# m1seminar.net
KiCad netlist of a schematic drawn in EAGLE
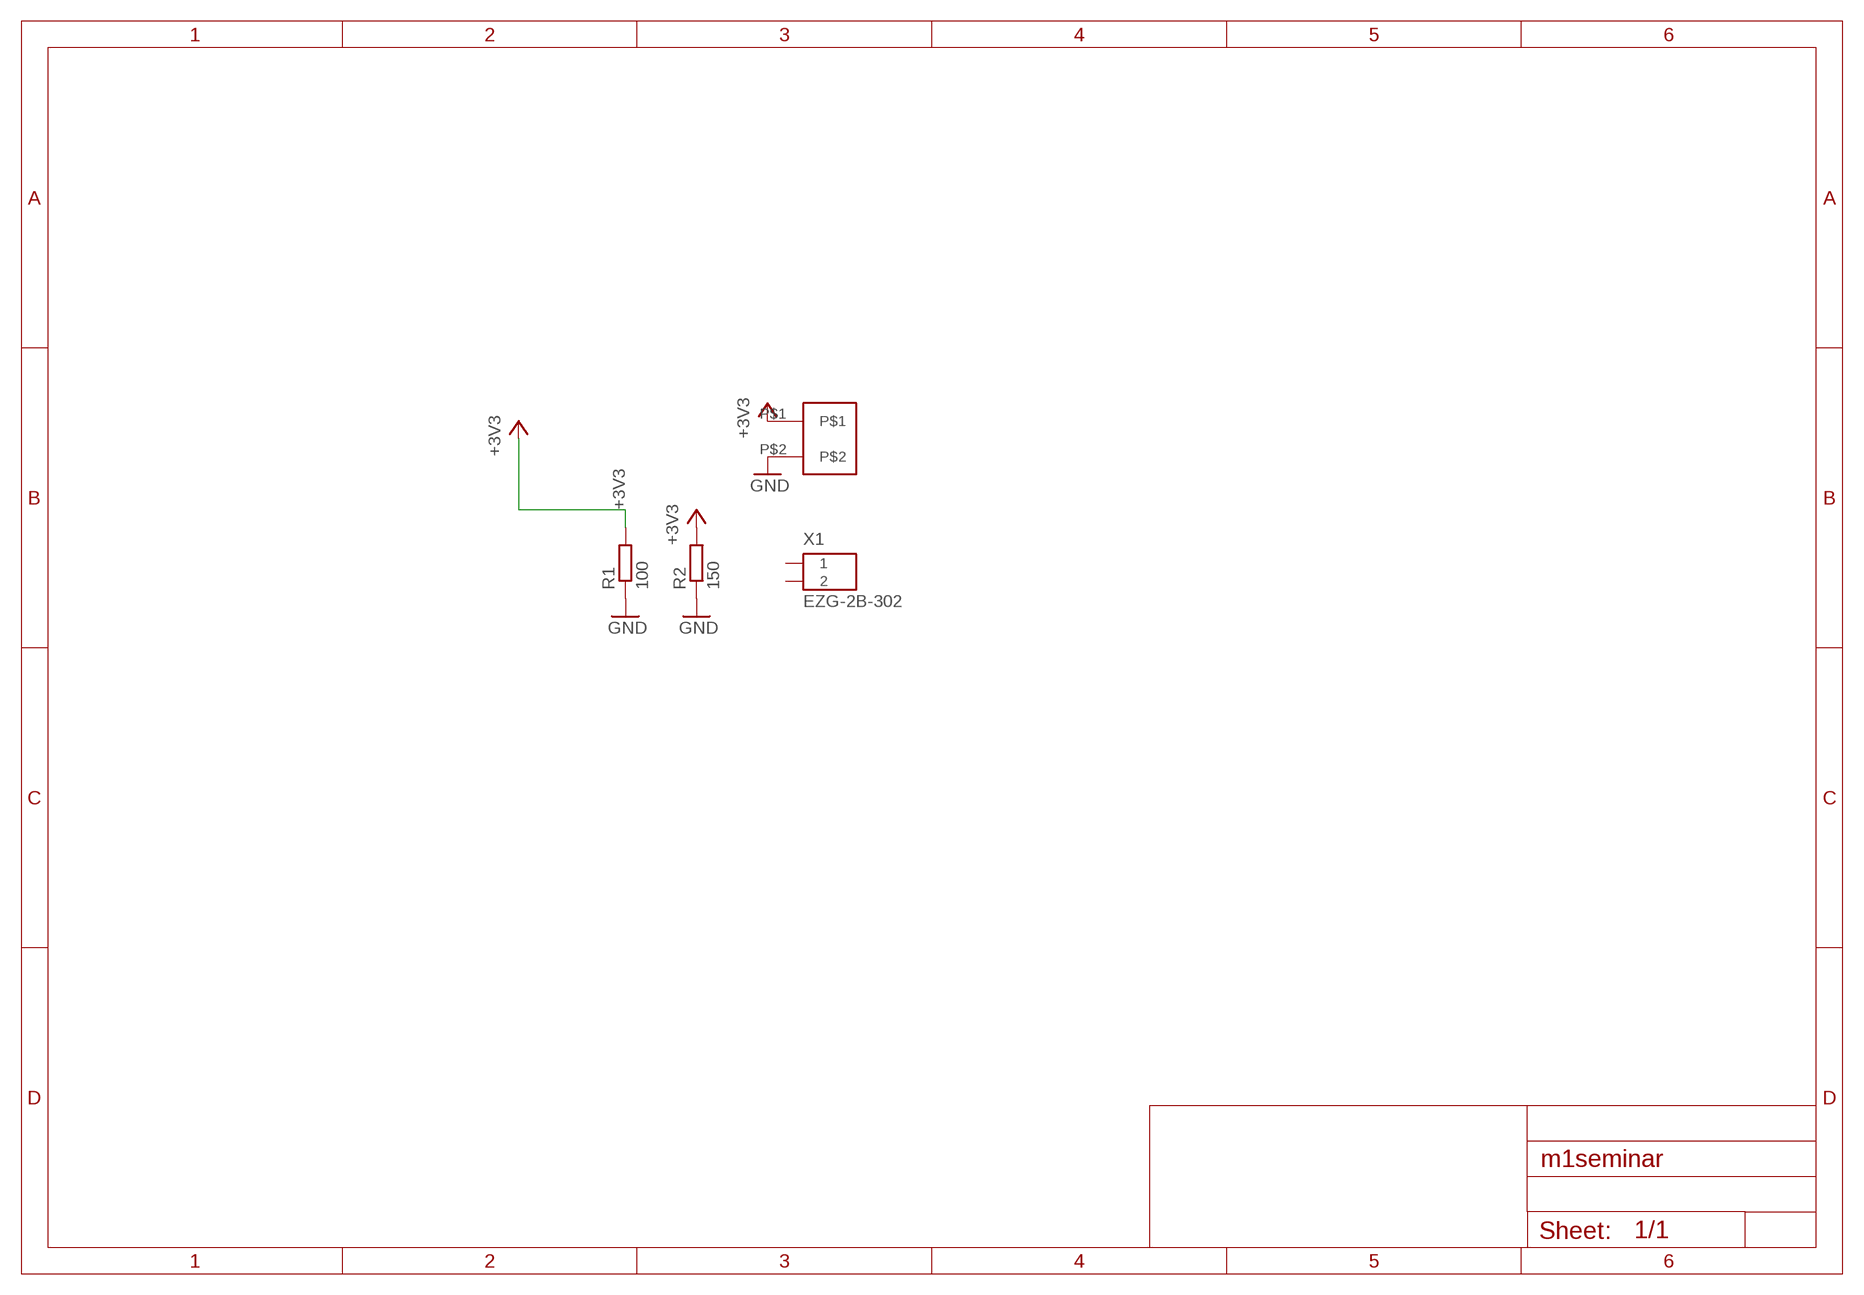
[diagram p0: schematic, sheet 1]

(export (version "E")
  (design (tool "Eeschema 10.0.6"))
  (components
    (comp (ref "R1")
      (value "100")
      (footprint "eagle-import:0204_7")
      (libsource (lib "eagle-import") (part "R-EU_0204/7"))
    )
    (comp (ref "R2")
      (value "150")
      (footprint "eagle-import:0204_7")
      (libsource (lib "eagle-import") (part "R-EU_0204/7"))
    )
    (comp (ref "U$1")
      (value "DF1E-2P")
      (footprint "eagle-import:DF1E-2P")
      (libsource (lib "eagle-import") (part "DF1E-2P"))
    )
    (comp (ref "X1")
      (value "EZG-2B-302")
      (footprint "eagle-import:EZG-2B-2K-302")
      (libsource (lib "eagle-import") (part "EZG-?-3022B"))
    )
  )
  (nets
    (net (code "1") (name "+3V3") (class "Default")
      (node (ref "R1") (pin "2") (pinfunction "2_2") (pintype "passive"))
      (node (ref "R2") (pin "2") (pinfunction "2_2") (pintype "passive"))
      (node (ref "U$1") (pin "P$1") (pinfunction "P$1_P$1") (pintype "bidirectional"))
    )
    (net (code "2") (name "GND") (class "Default")
      (node (ref "R1") (pin "1") (pinfunction "1_1") (pintype "passive"))
      (node (ref "R2") (pin "1") (pinfunction "1_1") (pintype "passive"))
      (node (ref "U$1") (pin "P$2") (pinfunction "P$2_P$2") (pintype "bidirectional"))
    )
    (net (code "3") (name "unconnected-(X1-Pad1)") (class "Default")
      (node (ref "X1") (pin "1") (pinfunction "1_1") (pintype "passive"))
    )
    (net (code "4") (name "unconnected-(X1-Pad2)") (class "Default")
      (node (ref "X1") (pin "2") (pinfunction "2_2") (pintype "passive"))
    )
  )
)
